# 1-Schematic_FireSmartFloorHeater_-_Contr.net
KiCad netlist of a schematic drawn in EasyEDA
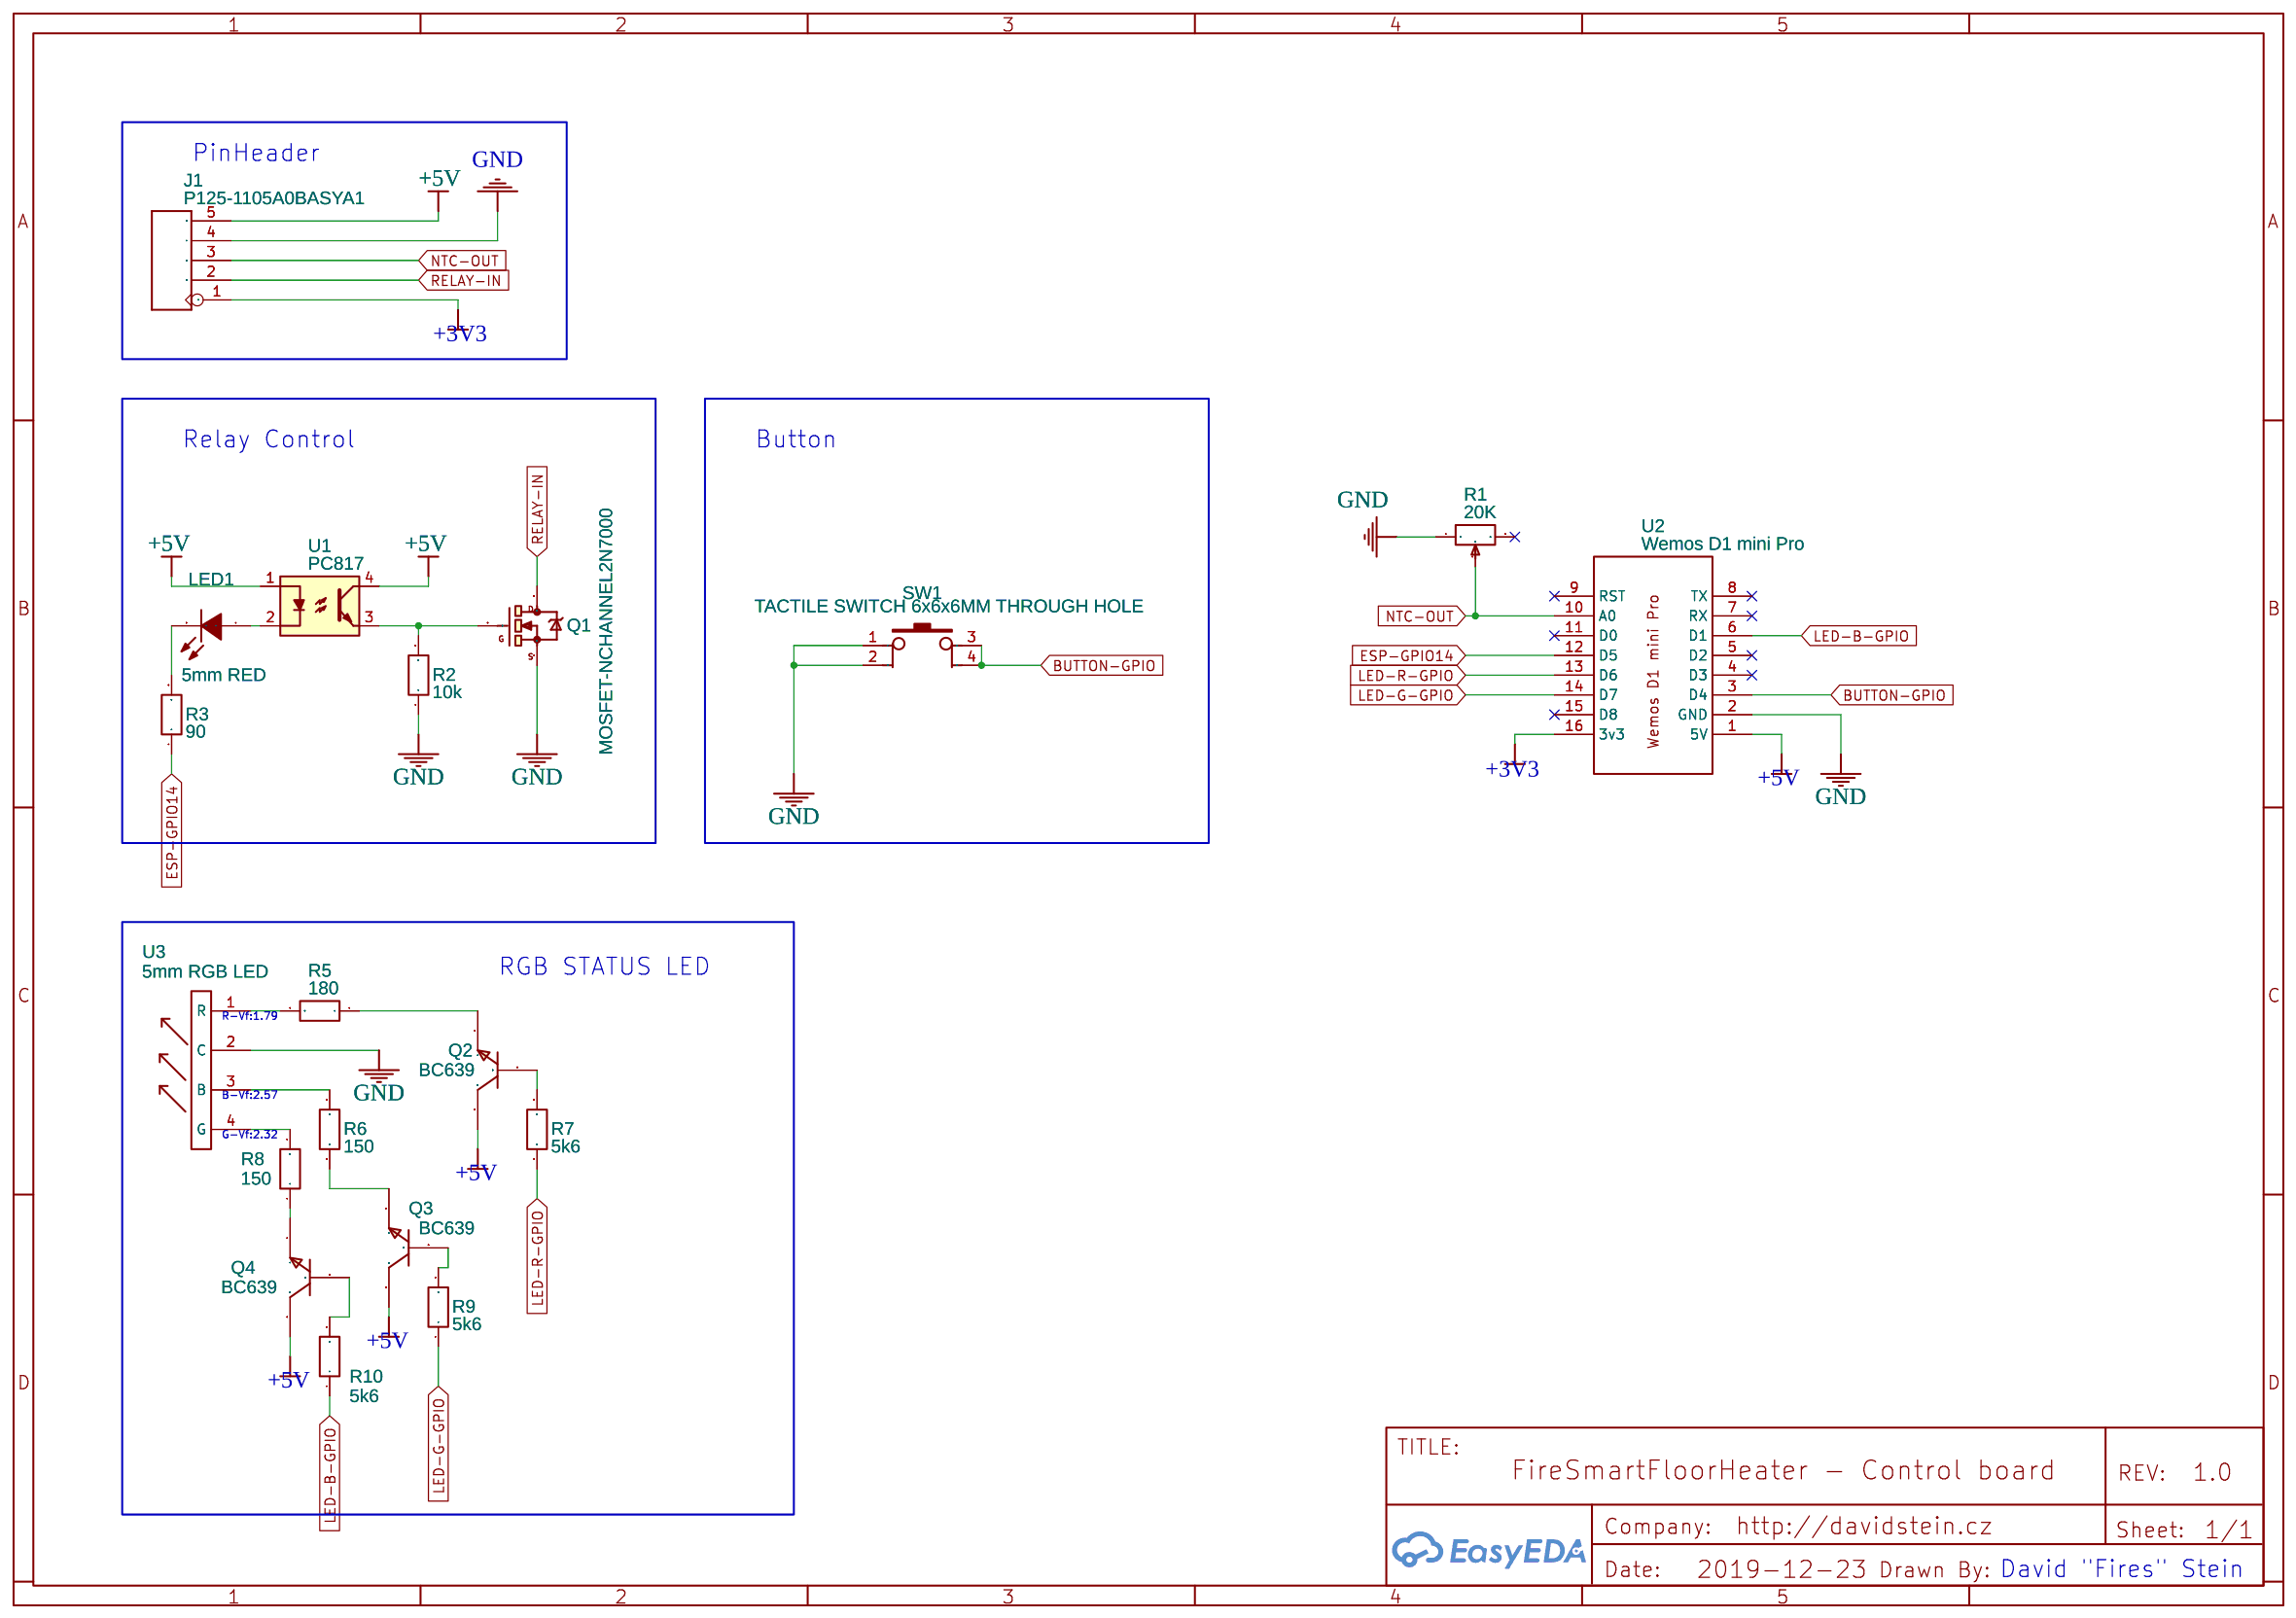
[diagram p0: ControlBoard]
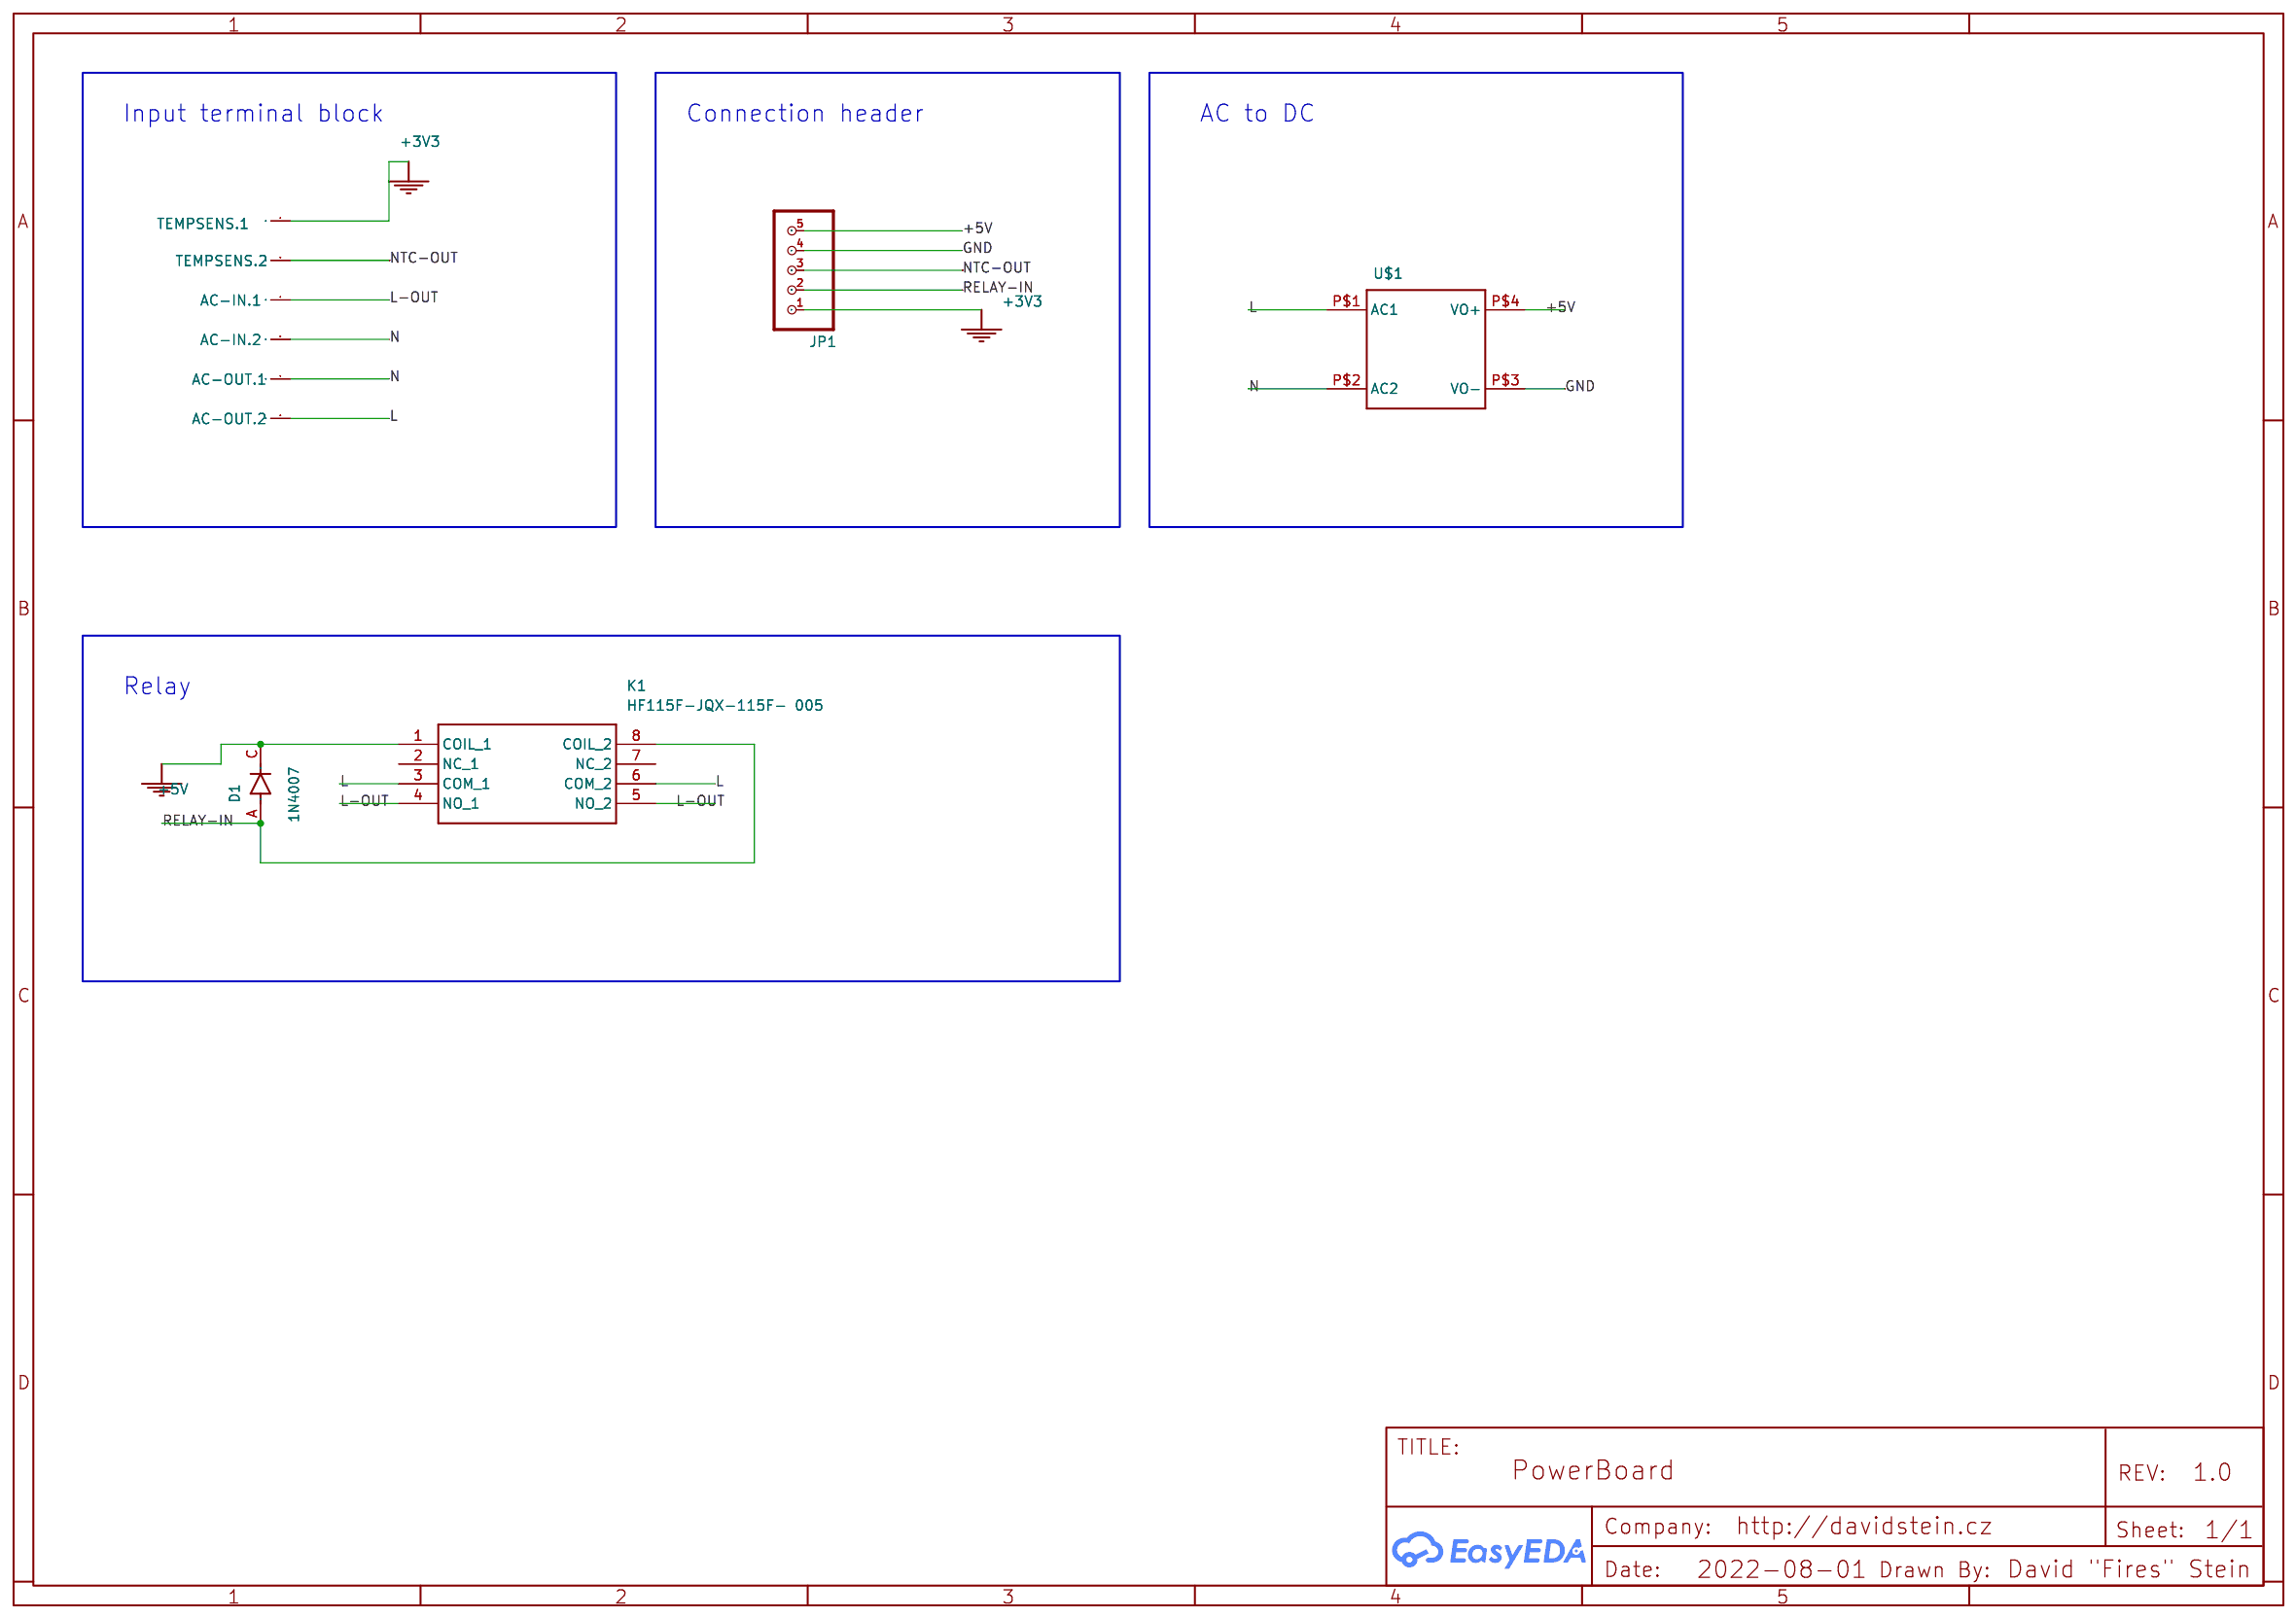
[diagram p1: PowerBoard]

(export (version "E")
  (design (tool "Eeschema 10.0.6"))
  (components
    (comp (ref "J1") (value "P125-1105A0BASYA1") (libsource (lib "") (part "Unknown_90_120")))
    (comp (ref "LED1")
      (value "5mm RED")
      (fields
        (field (name "BOM_Manufacturer Part") "204-10SURD/S530-A3")
        (field (name "BOM_Supplier Part") "C99772")
      )
      (libsource (lib "") (part "Unknown_100_310"))
    )
    (comp (ref "Q1") (value "MOSFET-NCHANNEL2N7000") (libsource (lib "") (part "Unknown_255_305")))
    (comp (ref "Q2") (value "BC639") (libsource (lib "") (part "Unknown_250_530")))
    (comp (ref "Q3") (value "BC639") (libsource (lib "") (part "Unknown_205_620")))
    (comp (ref "Q4") (value "BC639") (libsource (lib "") (part "Unknown_155_635")))
    (comp (ref "R1")
      (value "20K")
      (fields
        (field (name "BOM_Manufacturer Part") "3296W-1-203LF")
        (field (name "BOM_Supplier Part") "C34845")
      )
      (libsource (lib "") (part "3296W-1-203LF"))
    )
    (comp (ref "R2") (value "10k") (libsource (lib "") (part "Res_AXIAL-0.3(1/8W)_EU")))
    (comp (ref "R3") (value "90") (libsource (lib "") (part "Res_AXIAL-0.3(1/8W)_EU")))
    (comp (ref "R5") (value "180") (libsource (lib "") (part "Res_AXIAL-0.3(1/8W)_EU_1")))
    (comp (ref "R6") (value "150") (libsource (lib "") (part "Res_AXIAL-0.3(1/8W)_EU")))
    (comp (ref "R7") (value "5k6") (libsource (lib "") (part "Res_AXIAL-0.3(1/8W)_EU")))
    (comp (ref "R8") (value "150") (libsource (lib "") (part "Res_AXIAL-0.3(1/8W)_EU")))
    (comp (ref "R9") (value "5k6") (libsource (lib "") (part "Res_AXIAL-0.3(1/8W)_EU")))
    (comp (ref "R10") (value "5k6") (libsource (lib "") (part "Res_AXIAL-0.3(1/8W)_EU")))
    (comp (ref "SW1")
      (value "TACTILE SWITCH 6x6x6MM THROUGH HOLE")
      (fields
        (field (name "BOM_Manufacturer Part") "SMD Tactile Switch6*6*6mm")
        (field (name "BOM_Supplier Part") "C23873")
      )
      (libsource (lib "") (part "Unknown_460_315"))
    )
    (comp (ref "U1") (value "PC817") (libsource (lib "") (part "Unknown_135_285")))
    (comp (ref "U2") (value "Wemos D1 mini Pro") (libsource (lib "") (part "Unknown_800_360")))
    (comp (ref "U3") (value "5mm RGB LED") (libsource (lib "") (part "Unknown_100_510")))
    (comp (ref "AC-IN.1") (value "AK500/2") (libsource (lib "") (part "Unknown_120_-665")))
    (comp (ref "AC-IN.2") (value "AK500/2") (libsource (lib "") (part "Unknown_120_-645")))
    (comp (ref "AC-OUT.1") (value "AK500/2") (libsource (lib "") (part "Unknown_120_-625")))
    (comp (ref "AC-OUT.2") (value "AK500/2") (libsource (lib "") (part "Unknown_120_-605")))
    (comp (ref "D1") (value "1N4007") (libsource (lib "") (part "Unknown_125_-420")))
    (comp (ref "JP1") (value "PINHD-1X5") (libsource (lib "") (part "Unknown_390_-680")))
    (comp (ref "K1") (value "HF115F-JQX-115F- 005") (libsource (lib "") (part "Unknown_195_-440")))
    (comp (ref "TEMPSENS.1") (value "AK500/2") (libsource (lib "") (part "Unknown_120_-705")))
    (comp (ref "TEMPSENS.2") (value "AK500/2") (libsource (lib "") (part "Unknown_120_-685")))
    (comp (ref "U$1") (value "HLK-PM01") (libsource (lib "") (part "Unknown_715_-640")))
  )
  (nets
    (net (code "1") (name "+3V3") (class "Default")
      (node (ref "J1") (pin "1") (pinfunction "1_1") (pintype "unspecified"))
      (node (ref "JP1") (pin "1") (pinfunction "1_1") (pintype "bidirectional"))
      (node (ref "TEMPSENS.1") (pin "1") (pinfunction "KL_1") (pintype "bidirectional"))
      (node (ref "U2") (pin "16") (pinfunction "3v3_16") (pintype "unspecified"))
    )
    (net (code "2") (name "+5V") (class "Default")
      (node (ref "D1") (pin "C") (pinfunction "C_C") (pintype "bidirectional"))
      (node (ref "J1") (pin "5") (pinfunction "5_5") (pintype "unspecified"))
      (node (ref "JP1") (pin "5") (pinfunction "5_5") (pintype "bidirectional"))
      (node (ref "K1") (pin "1") (pinfunction "COIL_1_1") (pintype "bidirectional"))
      (node (ref "Q2") (pin "2") (pinfunction "C_2") (pintype "unspecified"))
      (node (ref "Q3") (pin "2") (pinfunction "C_2") (pintype "unspecified"))
      (node (ref "Q4") (pin "2") (pinfunction "C_2") (pintype "unspecified"))
      (node (ref "U$1") (pin "P$4") (pinfunction "VO+_P$4") (pintype "bidirectional"))
      (node (ref "U1") (pin "1") (pintype "unspecified"))
      (node (ref "U1") (pin "4") (pintype "unspecified"))
      (node (ref "U2") (pin "1") (pinfunction "5V_1") (pintype "unspecified"))
    )
    (net (code "3") (name "BUTTON-GPIO") (class "Default")
      (node (ref "SW1") (pin "3") (pinfunction "3_3") (pintype "input"))
      (node (ref "SW1") (pin "4") (pinfunction "4_4") (pintype "input"))
      (node (ref "U2") (pin "3") (pinfunction "D4_3") (pintype "unspecified"))
    )
    (net (code "4") (name "ESP-GPIO14") (class "Default")
      (node (ref "R3") (pin "1") (pinfunction "1_1") (pintype "unspecified"))
      (node (ref "U2") (pin "12") (pinfunction "D5_12") (pintype "unspecified"))
    )
    (net (code "5") (name "GND") (class "Default")
      (node (ref "J1") (pin "4") (pinfunction "4_4") (pintype "unspecified"))
      (node (ref "JP1") (pin "4") (pinfunction "4_4") (pintype "bidirectional"))
      (node (ref "Q1") (pin "1") (pinfunction "S_1") (pintype "unspecified"))
      (node (ref "R1") (pin "1") (pinfunction "1_1") (pintype "input"))
      (node (ref "R2") (pin "1") (pinfunction "1_1") (pintype "unspecified"))
      (node (ref "SW1") (pin "1") (pinfunction "1_1") (pintype "input"))
      (node (ref "SW1") (pin "2") (pinfunction "2_2") (pintype "input"))
      (node (ref "U$1") (pin "P$3") (pinfunction "VO-_P$3") (pintype "bidirectional"))
      (node (ref "U2") (pin "2") (pinfunction "GND_2") (pintype "unspecified"))
      (node (ref "U3") (pin "2") (pinfunction "C_2") (pintype "unspecified"))
    )
    (net (code "6") (name "L") (class "Default")
      (node (ref "AC-OUT.2") (pin "2") (pinfunction "KL_2") (pintype "bidirectional"))
      (node (ref "K1") (pin "3") (pinfunction "COM_1_3") (pintype "bidirectional"))
      (node (ref "K1") (pin "6") (pinfunction "COM_2_6") (pintype "bidirectional"))
      (node (ref "U$1") (pin "P$1") (pinfunction "AC1_P$1") (pintype "bidirectional"))
    )
    (net (code "7") (name "L-OUT") (class "Default")
      (node (ref "AC-IN.1") (pin "1") (pinfunction "KL_1") (pintype "bidirectional"))
      (node (ref "K1") (pin "4") (pinfunction "NO_1_4") (pintype "bidirectional"))
      (node (ref "K1") (pin "5") (pinfunction "NO_2_5") (pintype "bidirectional"))
    )
    (net (code "8") (name "LED-B-GPIO") (class "Default")
      (node (ref "R10") (pin "1") (pinfunction "1_1") (pintype "unspecified"))
      (node (ref "U2") (pin "6") (pinfunction "D1_6") (pintype "unspecified"))
    )
    (net (code "9") (name "LED-G-GPIO") (class "Default")
      (node (ref "R9") (pin "1") (pinfunction "1_1") (pintype "unspecified"))
      (node (ref "U2") (pin "14") (pinfunction "D7_14") (pintype "unspecified"))
    )
    (net (code "10") (name "LED-R-GPIO") (class "Default")
      (node (ref "R7") (pin "1") (pinfunction "1_1") (pintype "unspecified"))
      (node (ref "U2") (pin "13") (pinfunction "D6_13") (pintype "unspecified"))
    )
    (net (code "11") (name "N") (class "Default")
      (node (ref "AC-IN.2") (pin "2") (pinfunction "KL_2") (pintype "bidirectional"))
      (node (ref "AC-OUT.1") (pin "1") (pinfunction "KL_1") (pintype "bidirectional"))
      (node (ref "U$1") (pin "P$2") (pinfunction "AC2_P$2") (pintype "bidirectional"))
    )
    (net (code "12") (name "NTC-OUT") (class "Default")
      (node (ref "J1") (pin "3") (pinfunction "3_3") (pintype "unspecified"))
      (node (ref "JP1") (pin "3") (pinfunction "3_3") (pintype "bidirectional"))
      (node (ref "R1") (pin "2") (pinfunction "2_2") (pintype "input"))
      (node (ref "TEMPSENS.2") (pin "2") (pinfunction "KL_2") (pintype "bidirectional"))
      (node (ref "U2") (pin "10") (pinfunction "A0_10") (pintype "unspecified"))
    )
    (net (code "13") (name "Net-(LED1-A)") (class "Default")
      (node (ref "LED1") (pin "1") (pinfunction "A_1") (pintype "unspecified"))
      (node (ref "U1") (pin "2") (pintype "unspecified"))
    )
    (net (code "14") (name "Net-(LED1-K)") (class "Default")
      (node (ref "LED1") (pin "2") (pinfunction "K_2") (pintype "unspecified"))
      (node (ref "R3") (pin "2") (pinfunction "2_2") (pintype "unspecified"))
    )
    (net (code "15") (name "Net-(Q1-G)") (class "Default")
      (node (ref "Q1") (pin "2") (pinfunction "G_2") (pintype "unspecified"))
      (node (ref "R2") (pin "2") (pinfunction "2_2") (pintype "unspecified"))
      (node (ref "U1") (pin "3") (pintype "unspecified"))
    )
    (net (code "16") (name "Net-(Q2-B)") (class "Default")
      (node (ref "Q2") (pin "3") (pinfunction "B_3") (pintype "unspecified"))
      (node (ref "R7") (pin "2") (pinfunction "2_2") (pintype "unspecified"))
    )
    (net (code "17") (name "Net-(Q2-E)") (class "Default")
      (node (ref "Q2") (pin "1") (pinfunction "E_1") (pintype "unspecified"))
      (node (ref "R5") (pin "1") (pinfunction "1_1") (pintype "unspecified"))
    )
    (net (code "18") (name "Net-(Q3-B)") (class "Default")
      (node (ref "Q3") (pin "3") (pinfunction "B_3") (pintype "unspecified"))
      (node (ref "R9") (pin "2") (pinfunction "2_2") (pintype "unspecified"))
    )
    (net (code "19") (name "Net-(Q3-E)") (class "Default")
      (node (ref "Q3") (pin "1") (pinfunction "E_1") (pintype "unspecified"))
      (node (ref "R6") (pin "1") (pinfunction "1_1") (pintype "unspecified"))
    )
    (net (code "20") (name "Net-(Q4-B)") (class "Default")
      (node (ref "Q4") (pin "3") (pinfunction "B_3") (pintype "unspecified"))
      (node (ref "R10") (pin "2") (pinfunction "2_2") (pintype "unspecified"))
    )
    (net (code "21") (name "Net-(Q4-E)") (class "Default")
      (node (ref "Q4") (pin "1") (pinfunction "E_1") (pintype "unspecified"))
      (node (ref "R8") (pin "1") (pinfunction "1_1") (pintype "unspecified"))
    )
    (net (code "22") (name "Net-(U3-B)") (class "Default")
      (node (ref "R6") (pin "2") (pinfunction "2_2") (pintype "unspecified"))
      (node (ref "U3") (pin "3") (pinfunction "B_3") (pintype "unspecified"))
    )
    (net (code "23") (name "Net-(U3-G)") (class "Default")
      (node (ref "R8") (pin "2") (pinfunction "2_2") (pintype "unspecified"))
      (node (ref "U3") (pin "4") (pinfunction "G_4") (pintype "unspecified"))
    )
    (net (code "24") (name "Net-(U3-R)") (class "Default")
      (node (ref "R5") (pin "2") (pinfunction "2_2") (pintype "unspecified"))
      (node (ref "U3") (pin "1") (pinfunction "R_1") (pintype "unspecified"))
    )
    (net (code "25") (name "RELAY-IN") (class "Default")
      (node (ref "D1") (pin "A") (pinfunction "A_A") (pintype "bidirectional"))
      (node (ref "J1") (pin "2") (pinfunction "2_2") (pintype "unspecified"))
      (node (ref "JP1") (pin "2") (pinfunction "2_2") (pintype "bidirectional"))
      (node (ref "K1") (pin "8") (pinfunction "COIL_2_8") (pintype "bidirectional"))
      (node (ref "Q1") (pin "3") (pinfunction "D_3") (pintype "unspecified"))
    )
    (net (code "26") (name "unconnected-(K1-NC_1-Pad2)") (class "Default")
      (node (ref "K1") (pin "2") (pinfunction "NC_1_2") (pintype "bidirectional"))
    )
    (net (code "27") (name "unconnected-(K1-NC_2-Pad7)") (class "Default")
      (node (ref "K1") (pin "7") (pinfunction "NC_2_7") (pintype "bidirectional"))
    )
    (net (code "28") (name "unconnected-(R1-Pad3)") (class "Default")
      (node (ref "R1") (pin "3") (pinfunction "3_3") (pintype "input+no_connect"))
    )
    (net (code "29") (name "unconnected-(U2-D0-Pad11)") (class "Default")
      (node (ref "U2") (pin "11") (pinfunction "D0_11") (pintype "unspecified+no_connect"))
    )
    (net (code "30") (name "unconnected-(U2-D2-Pad5)") (class "Default")
      (node (ref "U2") (pin "5") (pinfunction "D2_5") (pintype "unspecified+no_connect"))
    )
    (net (code "31") (name "unconnected-(U2-D3-Pad4)") (class "Default")
      (node (ref "U2") (pin "4") (pinfunction "D3_4") (pintype "unspecified+no_connect"))
    )
    (net (code "32") (name "unconnected-(U2-D8-Pad15)") (class "Default")
      (node (ref "U2") (pin "15") (pinfunction "D8_15") (pintype "unspecified+no_connect"))
    )
    (net (code "33") (name "unconnected-(U2-RST-Pad9)") (class "Default")
      (node (ref "U2") (pin "9") (pinfunction "RST_9") (pintype "unspecified+no_connect"))
    )
    (net (code "34") (name "unconnected-(U2-RX-Pad7)") (class "Default")
      (node (ref "U2") (pin "7") (pinfunction "RX_7") (pintype "unspecified+no_connect"))
    )
    (net (code "35") (name "unconnected-(U2-TX-Pad8)") (class "Default")
      (node (ref "U2") (pin "8") (pinfunction "TX_8") (pintype "unspecified+no_connect"))
    )
  )
)
